# hw2.net
KiCad netlist of a schematic drawn in EAGLE
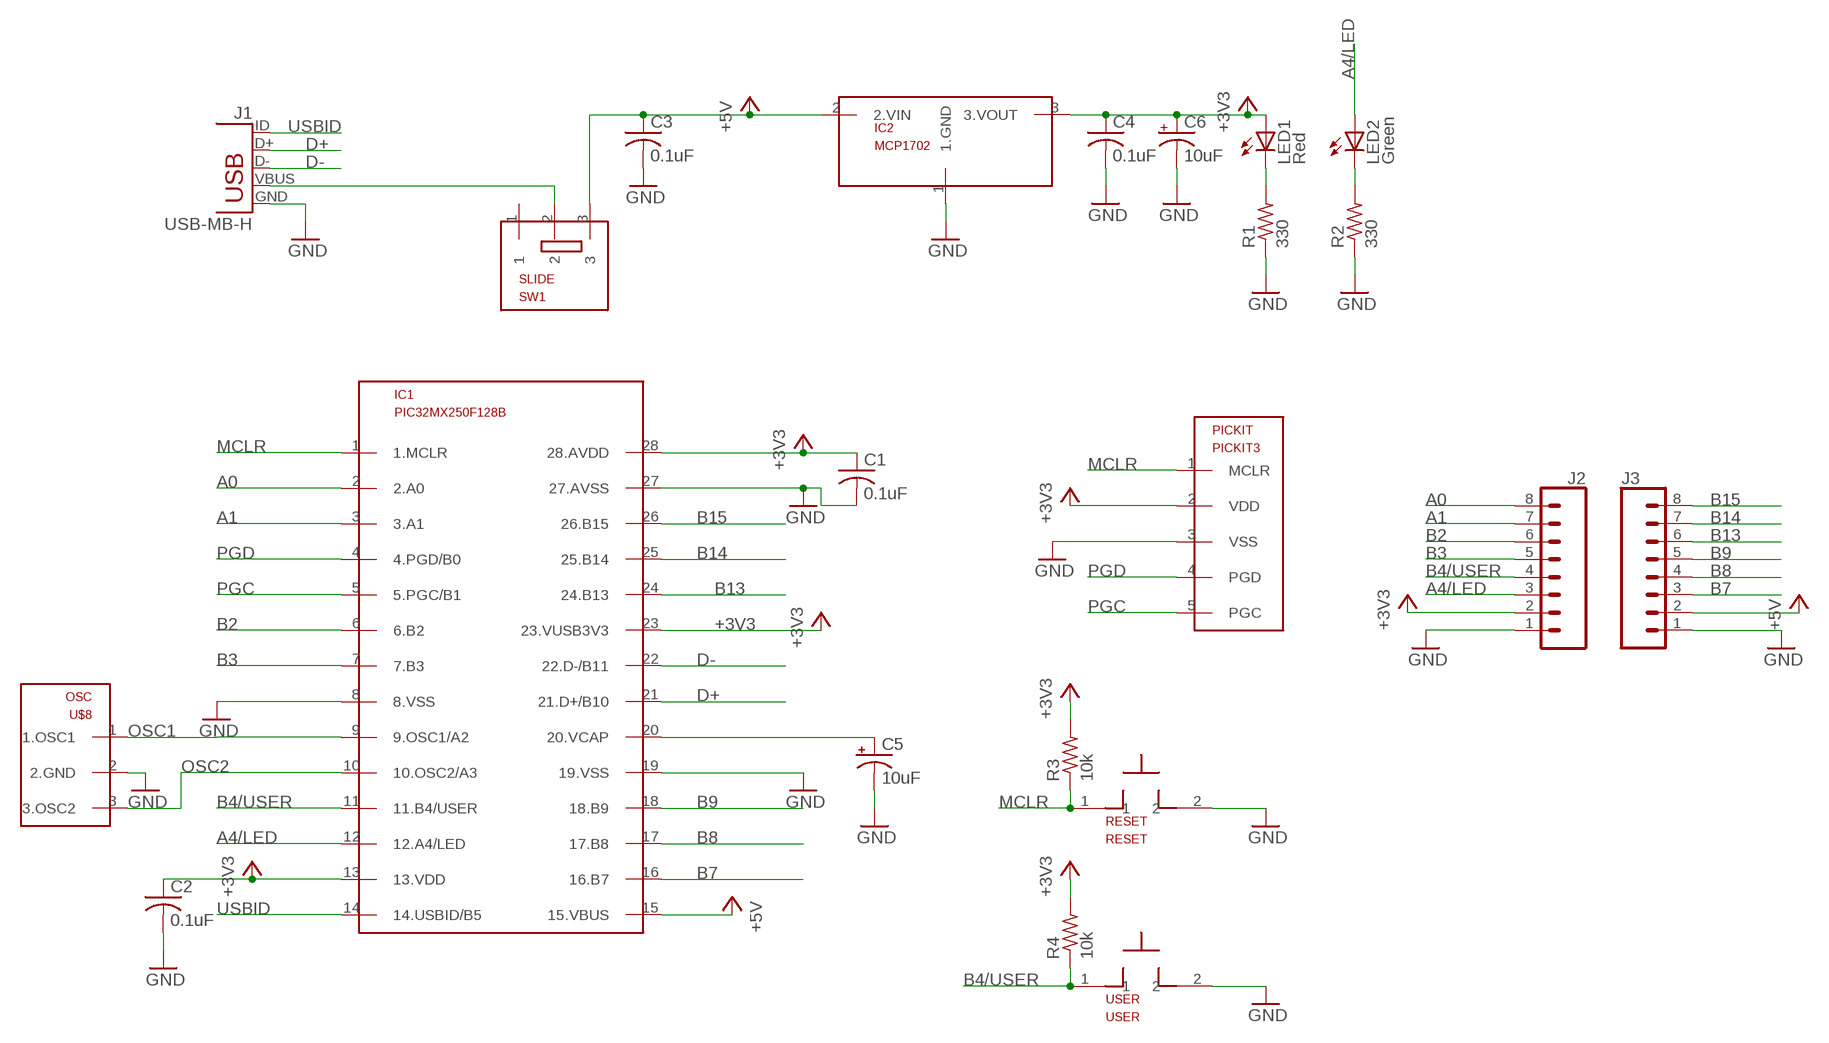
[diagram p0: schematic, sheet 1]

(export (version "E")
  (design (tool "Eeschema 10.0.6"))
  (components
    (comp (ref "C1")
      (value "0.1uF")
      (footprint "eagle-import:C025-025X050")
      (libsource (lib "eagle-import") (part "C-US025-025X050"))
    )
    (comp (ref "C2")
      (value "0.1uF")
      (footprint "eagle-import:C025-025X050")
      (libsource (lib "eagle-import") (part "C-US025-025X050"))
    )
    (comp (ref "C3")
      (value "0.1uF")
      (footprint "eagle-import:C025-025X050")
      (libsource (lib "eagle-import") (part "C-US025-025X050"))
    )
    (comp (ref "C4")
      (value "0.1uF")
      (footprint "eagle-import:C025-025X050")
      (libsource (lib "eagle-import") (part "C-US025-025X050"))
    )
    (comp (ref "C5")
      (value "10uF")
      (footprint "eagle-import:B45181B")
      (libsource (lib "eagle-import") (part "CPOL-USB45181B"))
    )
    (comp (ref "C6")
      (value "10uF")
      (footprint "eagle-import:B45181B")
      (libsource (lib "eagle-import") (part "CPOL-USB45181B"))
    )
    (comp (ref "IC1")
      (value "PIC32MX250F128B")
      (footprint "eagle-import:DIL28-3")
      (libsource (lib "eagle-import") (part "PIC32MX250F128B"))
    )
    (comp (ref "IC2")
      (value "MCP1702")
      (footprint "eagle-import:TO92")
      (libsource (lib "eagle-import") (part "MCP1702"))
    )
    (comp (ref "J1")
      (value "USB-MB-H")
      (footprint "eagle-import:USB-MB-H")
      (libsource (lib "eagle-import") (part "USB-MB-H"))
    )
    (comp (ref "J2")
      (value "CONN_08\"")
      (footprint "eagle-import:1X08")
      (libsource (lib "eagle-import") (part "CONN_08{dblquote}"))
    )
    (comp (ref "J3")
      (value "CONN_08\"")
      (footprint "eagle-import:1X08")
      (libsource (lib "eagle-import") (part "CONN_08{dblquote}"))
    )
    (comp (ref "LED1")
      (value "Red")
      (footprint "eagle-import:LED3MM")
      (libsource (lib "eagle-import") (part "LED3MM"))
    )
    (comp (ref "LED2")
      (value "Green")
      (footprint "eagle-import:LED3MM")
      (libsource (lib "eagle-import") (part "LED3MM"))
    )
    (comp (ref "PICKIT")
      (value "PICKIT3")
      (footprint "eagle-import:1X05")
      (libsource (lib "eagle-import") (part "PICKIT3"))
    )
    (comp (ref "R1")
      (value "330")
      (footprint "eagle-import:0207_10")
      (libsource (lib "eagle-import") (part "R-US_0207/10"))
    )
    (comp (ref "R2")
      (value "330")
      (footprint "eagle-import:0207_10")
      (libsource (lib "eagle-import") (part "R-US_0207/10"))
    )
    (comp (ref "R3")
      (value "10k")
      (footprint "eagle-import:0207_10")
      (libsource (lib "eagle-import") (part "R-US_0207/10"))
    )
    (comp (ref "R4")
      (value "10k")
      (footprint "eagle-import:0207_10")
      (libsource (lib "eagle-import") (part "R-US_0207/10"))
    )
    (comp (ref "RESET")
      (value "RESET")
      (footprint "eagle-import:PB")
      (libsource (lib "eagle-import") (part "PB"))
    )
    (comp (ref "SW1")
      (value "SLIDE")
      (footprint "eagle-import:SLIDE")
      (libsource (lib "eagle-import") (part "SLIDE"))
    )
    (comp (ref "U$8")
      (value "OSC")
      (footprint "eagle-import:OSC")
      (libsource (lib "eagle-import") (part "OSC"))
    )
    (comp (ref "USER")
      (value "USER")
      (footprint "eagle-import:PB")
      (libsource (lib "eagle-import") (part "PB"))
    )
  )
  (nets
    (net (code "1") (name "+3V3") (class "Default")
      (node (ref "C1") (pin "1") (pinfunction "1_1") (pintype "passive"))
      (node (ref "C2") (pin "1") (pinfunction "1_1") (pintype "passive"))
      (node (ref "C4") (pin "1") (pinfunction "1_1") (pintype "passive"))
      (node (ref "C6") (pin "+") (pinfunction "+_+") (pintype "passive"))
      (node (ref "IC1") (pin "13") (pinfunction "13.VDD_13") (pintype "bidirectional"))
      (node (ref "IC1") (pin "23") (pinfunction "23.VUSB3V3_23") (pintype "bidirectional"))
      (node (ref "IC1") (pin "28") (pinfunction "28.AVDD_28") (pintype "bidirectional"))
      (node (ref "IC2") (pin "3") (pinfunction "3.VOUT_3") (pintype "bidirectional"))
      (node (ref "J2") (pin "2") (pinfunction "2_2") (pintype "passive"))
      (node (ref "LED1") (pin "A") (pinfunction "A_A") (pintype "passive"))
      (node (ref "PICKIT") (pin "2") (pinfunction "VDD_2") (pintype "bidirectional"))
      (node (ref "R3") (pin "2") (pinfunction "2_2") (pintype "passive"))
      (node (ref "R4") (pin "2") (pinfunction "2_2") (pintype "passive"))
    )
    (net (code "2") (name "+5V") (class "Default")
      (node (ref "C3") (pin "1") (pinfunction "1_1") (pintype "passive"))
      (node (ref "IC1") (pin "15") (pinfunction "15.VBUS_15") (pintype "bidirectional"))
      (node (ref "IC2") (pin "2") (pinfunction "2.VIN_2") (pintype "bidirectional"))
      (node (ref "J3") (pin "2") (pinfunction "2_2") (pintype "passive"))
      (node (ref "SW1") (pin "3") (pinfunction "3_3") (pintype "bidirectional"))
    )
    (net (code "3") (name "/A0") (class "Default")
      (node (ref "IC1") (pin "2") (pinfunction "2.A0_2") (pintype "bidirectional"))
      (node (ref "J2") (pin "8") (pinfunction "8_8") (pintype "passive"))
    )
    (net (code "4") (name "/A1") (class "Default")
      (node (ref "IC1") (pin "3") (pinfunction "3.A1_3") (pintype "bidirectional"))
      (node (ref "J2") (pin "7") (pinfunction "7_7") (pintype "passive"))
    )
    (net (code "5") (name "/A4{slash}LED") (class "Default")
      (node (ref "IC1") (pin "12") (pinfunction "12.A4/LED_12") (pintype "bidirectional"))
      (node (ref "J2") (pin "3") (pinfunction "3_3") (pintype "passive"))
      (node (ref "LED2") (pin "A") (pinfunction "A_A") (pintype "passive"))
    )
    (net (code "6") (name "/B2") (class "Default")
      (node (ref "IC1") (pin "6") (pinfunction "6.B2_6") (pintype "bidirectional"))
      (node (ref "J2") (pin "6") (pinfunction "6_6") (pintype "passive"))
    )
    (net (code "7") (name "/B3") (class "Default")
      (node (ref "IC1") (pin "7") (pinfunction "7.B3_7") (pintype "bidirectional"))
      (node (ref "J2") (pin "5") (pinfunction "5_5") (pintype "passive"))
    )
    (net (code "8") (name "/B4{slash}USER") (class "Default")
      (node (ref "IC1") (pin "11") (pinfunction "11.B4/USER_11") (pintype "bidirectional"))
      (node (ref "J2") (pin "4") (pinfunction "4_4") (pintype "passive"))
      (node (ref "R4") (pin "1") (pinfunction "1_1") (pintype "passive"))
      (node (ref "USER") (pin "1") (pinfunction "1_1") (pintype "bidirectional"))
    )
    (net (code "9") (name "/B7") (class "Default")
      (node (ref "IC1") (pin "16") (pinfunction "16.B7_16") (pintype "bidirectional"))
      (node (ref "J3") (pin "3") (pinfunction "3_3") (pintype "passive"))
    )
    (net (code "10") (name "/B8") (class "Default")
      (node (ref "IC1") (pin "17") (pinfunction "17.B8_17") (pintype "bidirectional"))
      (node (ref "J3") (pin "4") (pinfunction "4_4") (pintype "passive"))
    )
    (net (code "11") (name "/B9") (class "Default")
      (node (ref "IC1") (pin "18") (pinfunction "18.B9_18") (pintype "bidirectional"))
      (node (ref "J3") (pin "5") (pinfunction "5_5") (pintype "passive"))
    )
    (net (code "12") (name "/B13") (class "Default")
      (node (ref "IC1") (pin "24") (pinfunction "24.B13_24") (pintype "bidirectional"))
      (node (ref "J3") (pin "6") (pinfunction "6_6") (pintype "passive"))
    )
    (net (code "13") (name "/B14") (class "Default")
      (node (ref "IC1") (pin "25") (pinfunction "25.B14_25") (pintype "bidirectional"))
      (node (ref "J3") (pin "7") (pinfunction "7_7") (pintype "passive"))
    )
    (net (code "14") (name "/B15") (class "Default")
      (node (ref "IC1") (pin "26") (pinfunction "26.B15_26") (pintype "bidirectional"))
      (node (ref "J3") (pin "8") (pinfunction "8_8") (pintype "passive"))
    )
    (net (code "15") (name "/D+") (class "Default")
      (node (ref "IC1") (pin "21") (pinfunction "21.D+/B10_21") (pintype "bidirectional"))
      (node (ref "J1") (pin "D+") (pinfunction "D+_D+") (pintype "bidirectional"))
    )
    (net (code "16") (name "/D-") (class "Default")
      (node (ref "IC1") (pin "22") (pinfunction "22.D-/B11_22") (pintype "bidirectional"))
      (node (ref "J1") (pin "D-") (pinfunction "D-_D-") (pintype "bidirectional"))
    )
    (net (code "17") (name "/MCLR") (class "Default")
      (node (ref "IC1") (pin "1") (pinfunction "1.MCLR_1") (pintype "bidirectional"))
      (node (ref "PICKIT") (pin "1") (pinfunction "MCLR_1") (pintype "bidirectional"))
      (node (ref "R3") (pin "1") (pinfunction "1_1") (pintype "passive"))
      (node (ref "RESET") (pin "1") (pinfunction "1_1") (pintype "bidirectional"))
    )
    (net (code "18") (name "/OSC1") (class "Default")
      (node (ref "IC1") (pin "9") (pinfunction "9.OSC1/A2_9") (pintype "bidirectional"))
      (node (ref "U$8") (pin "1") (pinfunction "1.OSC1_1") (pintype "bidirectional"))
    )
    (net (code "19") (name "/OSC2") (class "Default")
      (node (ref "IC1") (pin "10") (pinfunction "10.OSC2/A3_10") (pintype "bidirectional"))
      (node (ref "U$8") (pin "3") (pinfunction "3.OSC2_3") (pintype "bidirectional"))
    )
    (net (code "20") (name "/PGC") (class "Default")
      (node (ref "IC1") (pin "5") (pinfunction "5.PGC/B1_5") (pintype "bidirectional"))
      (node (ref "PICKIT") (pin "5") (pinfunction "PGC_5") (pintype "bidirectional"))
    )
    (net (code "21") (name "/PGD") (class "Default")
      (node (ref "IC1") (pin "4") (pinfunction "4.PGD/B0_4") (pintype "bidirectional"))
      (node (ref "PICKIT") (pin "4") (pinfunction "PGD_4") (pintype "bidirectional"))
    )
    (net (code "22") (name "/USBID") (class "Default")
      (node (ref "IC1") (pin "14") (pinfunction "14.USBID/B5_14") (pintype "bidirectional"))
      (node (ref "J1") (pin "ID") (pinfunction "ID_ID") (pintype "bidirectional"))
    )
    (net (code "23") (name "GND") (class "Default")
      (node (ref "C1") (pin "2") (pinfunction "2_2") (pintype "passive"))
      (node (ref "C2") (pin "2") (pinfunction "2_2") (pintype "passive"))
      (node (ref "C3") (pin "2") (pinfunction "2_2") (pintype "passive"))
      (node (ref "C4") (pin "2") (pinfunction "2_2") (pintype "passive"))
      (node (ref "C5") (pin "-") (pinfunction "-_-") (pintype "passive"))
      (node (ref "C6") (pin "-") (pinfunction "-_-") (pintype "passive"))
      (node (ref "IC1") (pin "19") (pinfunction "19.VSS_19") (pintype "bidirectional"))
      (node (ref "IC1") (pin "27") (pinfunction "27.AVSS_27") (pintype "bidirectional"))
      (node (ref "IC1") (pin "8") (pinfunction "8.VSS_8") (pintype "bidirectional"))
      (node (ref "IC2") (pin "1") (pinfunction "1.GND_1") (pintype "bidirectional"))
      (node (ref "J1") (pin "GND") (pinfunction "GND_GND") (pintype "bidirectional"))
      (node (ref "J2") (pin "1") (pinfunction "1_1") (pintype "passive"))
      (node (ref "J3") (pin "1") (pinfunction "1_1") (pintype "passive"))
      (node (ref "PICKIT") (pin "3") (pinfunction "VSS_3") (pintype "bidirectional"))
      (node (ref "R1") (pin "1") (pinfunction "1_1") (pintype "passive"))
      (node (ref "R2") (pin "1") (pinfunction "1_1") (pintype "passive"))
      (node (ref "RESET") (pin "2") (pinfunction "2_2") (pintype "bidirectional"))
      (node (ref "U$8") (pin "2") (pinfunction "2.GND_2") (pintype "bidirectional"))
      (node (ref "USER") (pin "2") (pinfunction "2_2") (pintype "bidirectional"))
    )
    (net (code "24") (name "Net-(IC1-20.VCAP)") (class "Default")
      (node (ref "C5") (pin "+") (pinfunction "+_+") (pintype "passive"))
      (node (ref "IC1") (pin "20") (pinfunction "20.VCAP_20") (pintype "bidirectional"))
    )
    (net (code "25") (name "Net-(J1-PadVBUS)") (class "Default")
      (node (ref "J1") (pin "VBUS") (pinfunction "VBUS_VBUS") (pintype "bidirectional"))
      (node (ref "SW1") (pin "2") (pinfunction "2_2") (pintype "bidirectional"))
    )
    (net (code "26") (name "Net-(LED1-C)") (class "Default")
      (node (ref "LED1") (pin "K") (pinfunction "C_K") (pintype "passive"))
      (node (ref "R1") (pin "2") (pinfunction "2_2") (pintype "passive"))
    )
    (net (code "27") (name "Net-(LED2-C)") (class "Default")
      (node (ref "LED2") (pin "K") (pinfunction "C_K") (pintype "passive"))
      (node (ref "R2") (pin "2") (pinfunction "2_2") (pintype "passive"))
    )
    (net (code "28") (name "unconnected-(SW1-Pad1)") (class "Default")
      (node (ref "SW1") (pin "1") (pinfunction "1_1") (pintype "bidirectional"))
    )
  )
)
